# Ex_Sensors.net
KiCad netlist of a schematic drawn in EAGLE
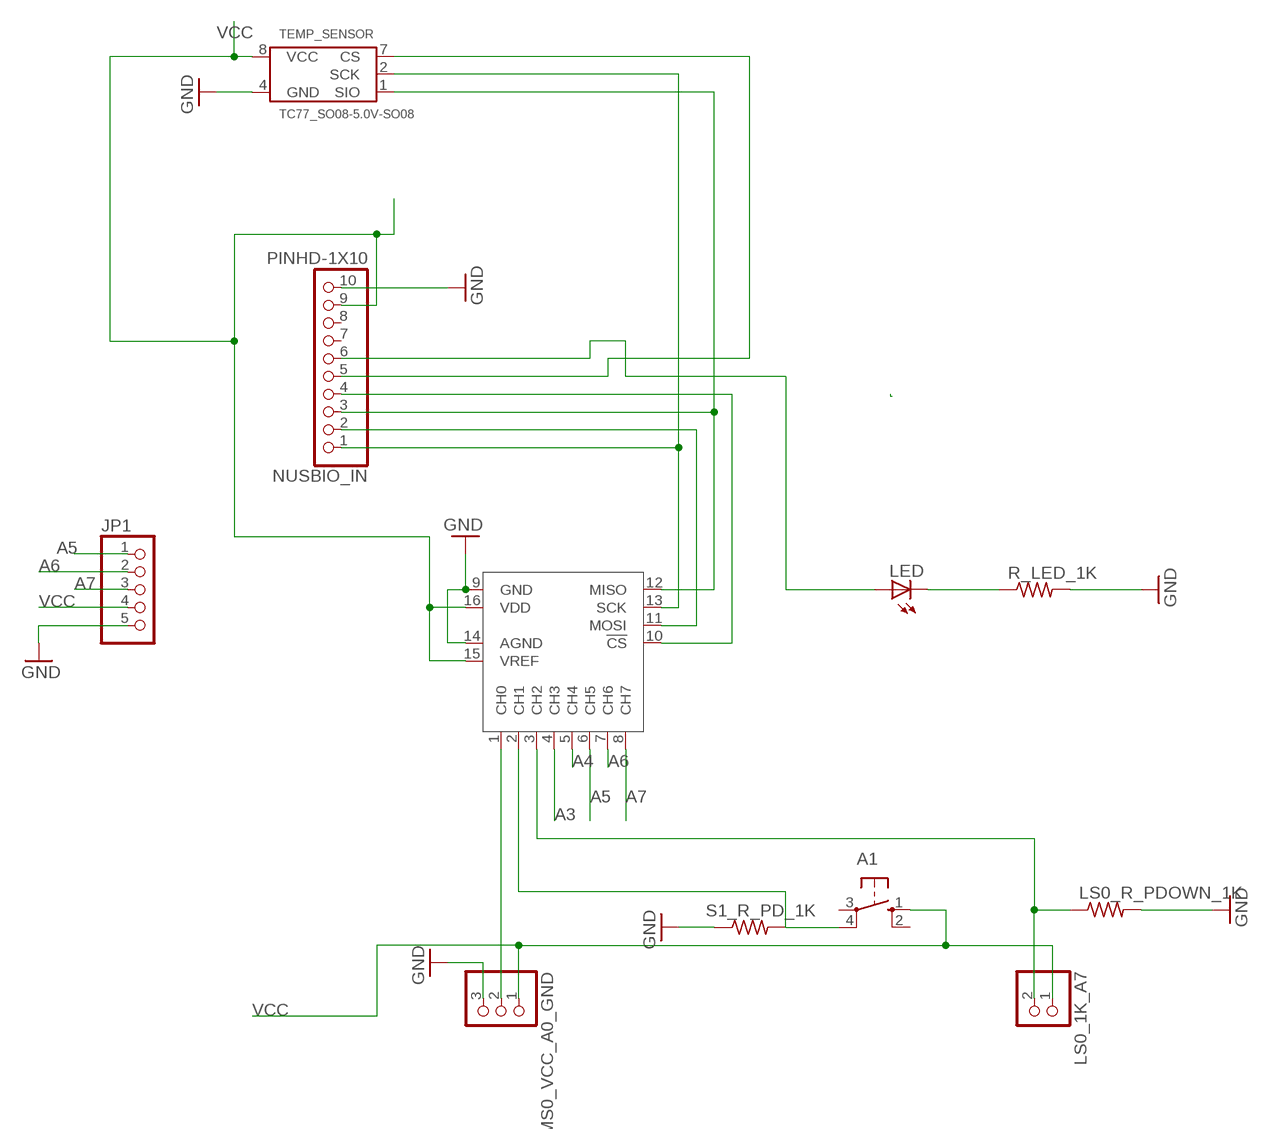
[diagram p0: schematic, sheet 1]

(export (version "E")
  (design (tool "Eeschema 10.0.6"))
  (components
    (comp (ref "A1")
      (value "10-XX")
      (footprint "eagle-import:B3F-10XX")
      (fields (field (name "MPN") "B3F-1000"))
      (libsource (lib "eagle-import") (part "10-XX"))
    )
    (comp (ref "JP1")
      (value "PINHD-1X5")
      (footprint "eagle-import:1X05")
      (libsource (lib "eagle-import") (part "PINHD-1X5"))
    )
    (comp (ref "LED")
      (value "LEDCHIPLED_0805")
      (footprint "eagle-import:CHIPLED_0805")
      (libsource (lib "eagle-import") (part "LEDCHIPLED_0805"))
    )
    (comp (ref "LS0_1K_A7")
      (value "PINHD-1X2")
      (footprint "eagle-import:1X02")
      (libsource (lib "eagle-import") (part "PINHD-1X2"))
    )
    (comp (ref "LS0_R_PDOWN_1K")
      (value "R-US_R0805")
      (footprint "eagle-import:R0805")
      (libsource (lib "eagle-import") (part "R-US_R0805"))
    )
    (comp (ref "MS0_VCC_A0_GND")
      (value "PINHD-1X3")
      (footprint "eagle-import:1X03")
      (libsource (lib "eagle-import") (part "PINHD-1X3"))
    )
    (comp (ref "NUSBIO_IN")
      (value "PINHD-1X10")
      (footprint "eagle-import:1X10-BIG")
      (libsource (lib "eagle-import") (part "PINHD-1X10"))
    )
    (comp (ref "R_LED_1K")
      (value "R-US_R0805")
      (footprint "eagle-import:R0805")
      (libsource (lib "eagle-import") (part "R-US_R0805"))
    )
    (comp (ref "S1_R_PD_1K")
      (value "R-US_R0805")
      (footprint "eagle-import:R0805")
      (libsource (lib "eagle-import") (part "R-US_R0805"))
    )
    (comp (ref "TEMP_SENSOR")
      (value "TC77_SO08-5.0V-SO08")
      (footprint "eagle-import:SO-08")
      (fields (field (name "MPN") "TC77-5.0MOA"))
      (libsource (lib "eagle-import") (part "TC77_SO08SO08-5.0V-"))
    )
    (comp (ref "U$1")
      (value "MCP3008SL")
      (footprint "eagle-import:SO16")
      (libsource (lib "eagle-import") (part "MCP3008SL"))
    )
  )
  (nets
    (net (code "1") (name "/A3") (class "Default")
      (node (ref "U$1") (pin "4") (pinfunction "CH3_4") (pintype "input"))
    )
    (net (code "2") (name "/A4") (class "Default")
      (node (ref "U$1") (pin "5") (pinfunction "CH4_5") (pintype "input"))
    )
    (net (code "3") (name "/A5") (class "Default")
      (node (ref "JP1") (pin "1") (pinfunction "1_1") (pintype "passive"))
      (node (ref "U$1") (pin "6") (pinfunction "CH5_6") (pintype "input"))
    )
    (net (code "4") (name "/A6") (class "Default")
      (node (ref "JP1") (pin "2") (pinfunction "2_2") (pintype "passive"))
      (node (ref "U$1") (pin "7") (pinfunction "CH6_7") (pintype "input"))
    )
    (net (code "5") (name "/A7") (class "Default")
      (node (ref "JP1") (pin "3") (pinfunction "3_3") (pintype "passive"))
      (node (ref "U$1") (pin "8") (pinfunction "CH7_8") (pintype "input"))
    )
    (net (code "6") (name "/VCC") (class "Default")
      (node (ref "A1") (pin "1") (pinfunction "S_1") (pintype "passive"))
      (node (ref "JP1") (pin "4") (pinfunction "4_4") (pintype "passive"))
      (node (ref "LS0_1K_A7") (pin "1") (pinfunction "1_1") (pintype "passive"))
      (node (ref "MS0_VCC_A0_GND") (pin "1") (pinfunction "1_1") (pintype "passive"))
      (node (ref "NUSBIO_IN") (pin "9") (pinfunction "9_9") (pintype "passive"))
      (node (ref "TEMP_SENSOR") (pin "8") (pinfunction "VCC_8") (pintype "power_in"))
      (node (ref "U$1") (pin "15") (pinfunction "VREF_15") (pintype "power_in"))
      (node (ref "U$1") (pin "16") (pinfunction "VDD_16") (pintype "power_in"))
    )
    (net (code "7") (name "GND") (class "Default")
      (node (ref "JP1") (pin "5") (pinfunction "5_5") (pintype "passive"))
      (node (ref "LS0_R_PDOWN_1K") (pin "2") (pinfunction "2_2") (pintype "passive"))
      (node (ref "MS0_VCC_A0_GND") (pin "3") (pinfunction "3_3") (pintype "passive"))
      (node (ref "NUSBIO_IN") (pin "10") (pinfunction "10_10") (pintype "passive"))
      (node (ref "R_LED_1K") (pin "2") (pinfunction "2_2") (pintype "passive"))
      (node (ref "S1_R_PD_1K") (pin "1") (pinfunction "1_1") (pintype "passive"))
      (node (ref "TEMP_SENSOR") (pin "4") (pinfunction "GND_4") (pintype "power_in"))
      (node (ref "U$1") (pin "14") (pinfunction "AGND_14") (pintype "power_in"))
      (node (ref "U$1") (pin "9") (pinfunction "GND_9") (pintype "power_in"))
    )
    (net (code "8") (name "Net-(A1-P1)") (class "Default")
      (node (ref "A1") (pin "4") (pinfunction "P1_4") (pintype "passive"))
      (node (ref "S1_R_PD_1K") (pin "2") (pinfunction "2_2") (pintype "passive"))
      (node (ref "U$1") (pin "2") (pinfunction "CH1_2") (pintype "input"))
    )
    (net (code "9") (name "Net-(LED-PadA)") (class "Default")
      (node (ref "LED") (pin "A") (pinfunction "A_A") (pintype "passive"))
      (node (ref "NUSBIO_IN") (pin "6") (pinfunction "6_6") (pintype "passive"))
    )
    (net (code "10") (name "Net-(LED-PadC)") (class "Default")
      (node (ref "LED") (pin "C") (pinfunction "C_C") (pintype "passive"))
      (node (ref "R_LED_1K") (pin "1") (pinfunction "1_1") (pintype "passive"))
    )
    (net (code "11") (name "Net-(TEMP_SENSOR-CS)") (class "Default")
      (node (ref "NUSBIO_IN") (pin "5") (pinfunction "5_5") (pintype "passive"))
      (node (ref "TEMP_SENSOR") (pin "7") (pinfunction "CS_7") (pintype "bidirectional"))
    )
    (net (code "12") (name "Net-(TEMP_SENSOR-SCK)") (class "Default")
      (node (ref "NUSBIO_IN") (pin "1") (pinfunction "1_1") (pintype "passive"))
      (node (ref "TEMP_SENSOR") (pin "2") (pinfunction "SCK_2") (pintype "bidirectional"))
      (node (ref "U$1") (pin "13") (pinfunction "SCK_13") (pintype "input"))
    )
    (net (code "13") (name "Net-(TEMP_SENSOR-SIO)") (class "Default")
      (node (ref "NUSBIO_IN") (pin "3") (pinfunction "3_3") (pintype "passive"))
      (node (ref "TEMP_SENSOR") (pin "1") (pinfunction "SIO_1") (pintype "bidirectional"))
      (node (ref "U$1") (pin "12") (pinfunction "MISO_12") (pintype "output"))
    )
    (net (code "14") (name "Net-(U$1-CH0)") (class "Default")
      (node (ref "MS0_VCC_A0_GND") (pin "2") (pinfunction "2_2") (pintype "passive"))
      (node (ref "U$1") (pin "1") (pinfunction "CH0_1") (pintype "input"))
    )
    (net (code "15") (name "Net-(U$1-CH2)") (class "Default")
      (node (ref "LS0_1K_A7") (pin "2") (pinfunction "2_2") (pintype "passive"))
      (node (ref "LS0_R_PDOWN_1K") (pin "1") (pinfunction "1_1") (pintype "passive"))
      (node (ref "U$1") (pin "3") (pinfunction "CH2_3") (pintype "input"))
    )
    (net (code "16") (name "Net-(U$1-MOSI)") (class "Default")
      (node (ref "NUSBIO_IN") (pin "2") (pinfunction "2_2") (pintype "passive"))
      (node (ref "U$1") (pin "11") (pinfunction "MOSI_11") (pintype "input"))
    )
    (net (code "17") (name "Net-(U$1-~{CS})") (class "Default")
      (node (ref "NUSBIO_IN") (pin "4") (pinfunction "4_4") (pintype "passive"))
      (node (ref "U$1") (pin "10") (pinfunction "~{CS}_10") (pintype "input"))
    )
    (net (code "18") (name "unconnected-(A1-P-Pad3)") (class "Default")
      (node (ref "A1") (pin "3") (pinfunction "P_3") (pintype "passive"))
    )
    (net (code "19") (name "unconnected-(A1-S1-Pad2)") (class "Default")
      (node (ref "A1") (pin "2") (pinfunction "S1_2") (pintype "passive"))
    )
    (net (code "20") (name "unconnected-(NUSBIO_IN-Pad7)") (class "Default")
      (node (ref "NUSBIO_IN") (pin "7") (pinfunction "7_7") (pintype "passive"))
    )
    (net (code "21") (name "unconnected-(NUSBIO_IN-Pad8)") (class "Default")
      (node (ref "NUSBIO_IN") (pin "8") (pinfunction "8_8") (pintype "passive"))
    )
  )
)
